# Integrated_LED.net
KiCad netlist of a schematic drawn in Altium Designer
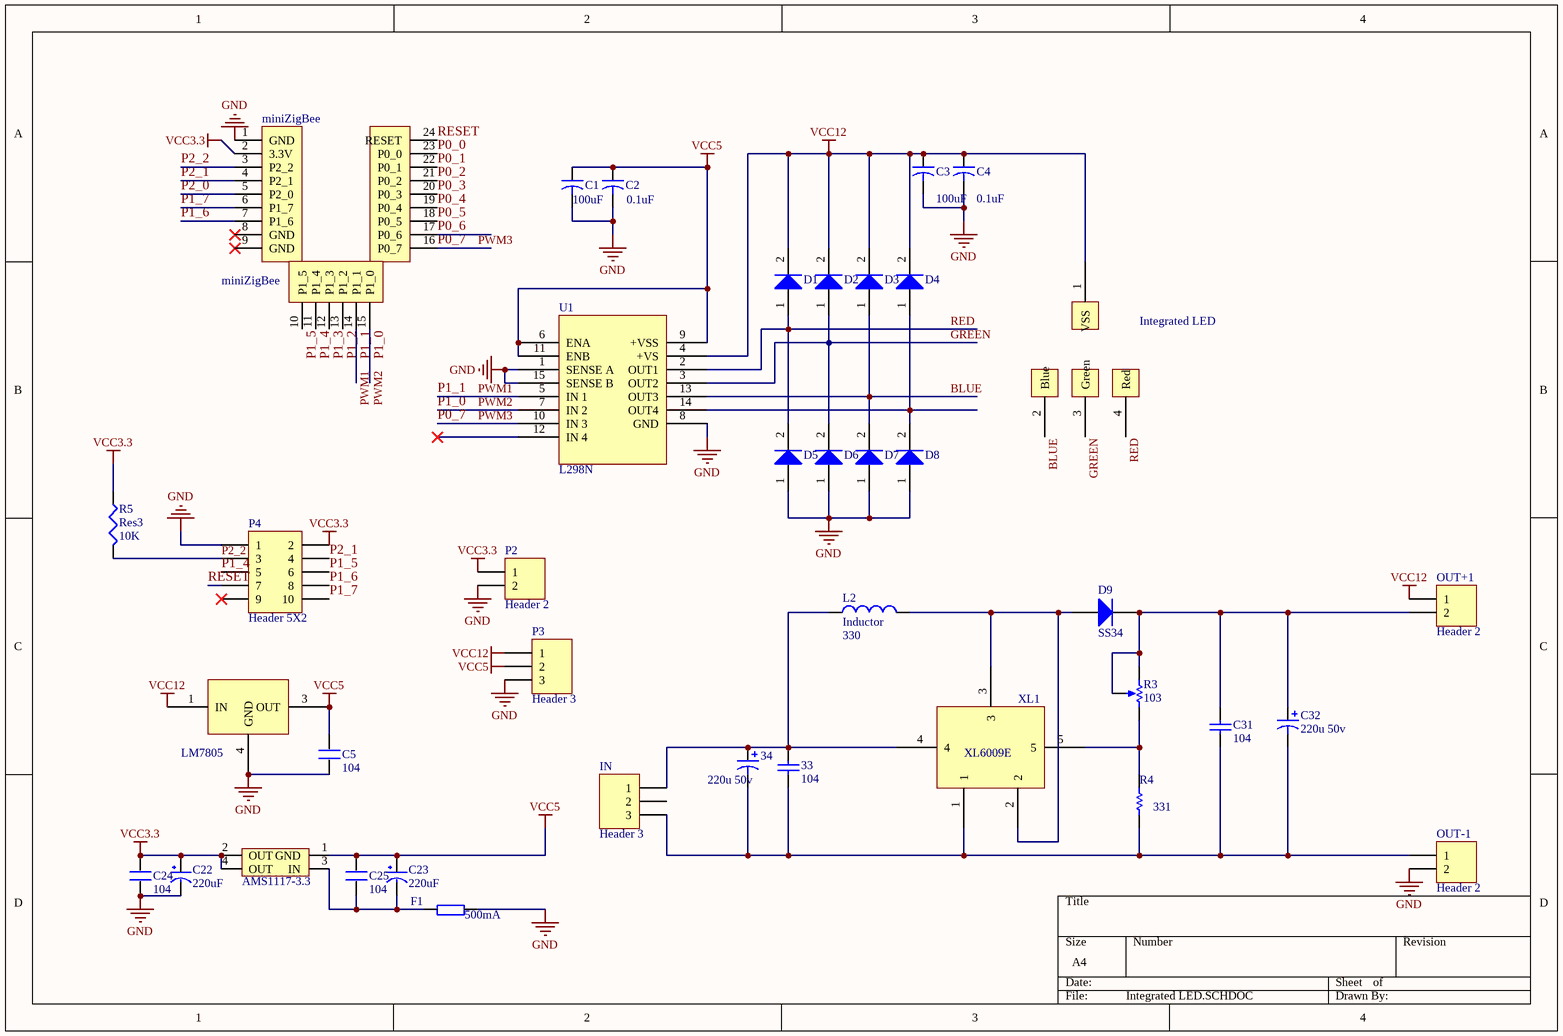
[diagram p0: Integrated LED.SCHDOC]

(export (version "E")
  (design (tool "Eeschema 10.0.6"))
  (components
    (comp (ref "33")
      (value "104")
      (footprint "0805")
      (description "Capacitor")
      (fields (field (name "PUBLISHER") "Altium Limited"))
      (libsource (lib "Miscellaneous Devices") (part "Cap"))
    )
    (comp (ref "34")
      (value "220u 50v")
      (footprint "贴片电解电容")
      (description "Polarized Capacitor (Radial)")
      (fields (field (name "PUBLISHER") "Altium Limited"))
      (libsource (lib "Miscellaneous Devices") (part "Cap Pol1"))
    )
    (comp (ref "C1")
      (value "100uF")
      (footprint "PCBComponent_1")
      (description "Capacitor")
      (fields (field (name "PUBLISHER") "Altium Limited"))
      (libsource (lib "Miscellaneous Devices") (part "Cap2"))
    )
    (comp (ref "C2")
      (value "0.1uF")
      (footprint "PCBComponent_1")
      (description "Capacitor")
      (fields (field (name "PUBLISHER") "Altium Limited"))
      (libsource (lib "Miscellaneous Devices") (part "Cap2"))
    )
    (comp (ref "C3")
      (value "100uF")
      (footprint "PCBComponent_1")
      (description "Capacitor")
      (fields (field (name "PUBLISHER") "Altium Limited"))
      (libsource (lib "Miscellaneous Devices") (part "Cap2"))
    )
    (comp (ref "C4")
      (value "0.1uF")
      (footprint "PCBComponent_1")
      (description "Capacitor")
      (fields (field (name "PUBLISHER") "Altium Limited"))
      (libsource (lib "Miscellaneous Devices") (part "Cap2"))
    )
    (comp (ref "C5") (value "104") (footprint "0603P") (libsource (lib "my Integrated lib ") (part "C")))
    (comp (ref "C22")
      (value "220uF")
      (footprint "CC6.56.5")
      (libsource (lib "MiniSTM32 V2.0封装库") (part "CAP"))
    )
    (comp (ref "C23")
      (value "220uF")
      (footprint "CC6.56.5")
      (libsource (lib "MiniSTM32 V2.0封装库") (part "CAP"))
    )
    (comp (ref "C24") (value "104") (footprint "0603P") (libsource (lib "MiniSTM32 V2.0封装库") (part "C")))
    (comp (ref "C25") (value "104") (footprint "0603P") (libsource (lib "MiniSTM32 V2.0封装库") (part "C")))
    (comp (ref "C31")
      (value "104")
      (footprint "0805")
      (description "Capacitor")
      (fields (field (name "PUBLISHER") "Altium Limited"))
      (libsource (lib "Miscellaneous Devices") (part "Cap"))
    )
    (comp (ref "C32")
      (value "220u 50v")
      (footprint "贴片电解电容")
      (description "Polarized Capacitor (Radial)")
      (fields (field (name "PUBLISHER") "Altium Limited"))
      (libsource (lib "Miscellaneous Devices") (part "Cap Pol1"))
    )
    (comp (ref "D1")
      (value "IN4007")
      (footprint "IN4007")
      (libsource (lib "my Integrated lib ") (part "IN4007"))
    )
    (comp (ref "D2")
      (value "IN4007")
      (footprint "IN4007")
      (libsource (lib "my Integrated lib ") (part "IN4007"))
    )
    (comp (ref "D3")
      (value "IN4007")
      (footprint "IN4007")
      (libsource (lib "my Integrated lib ") (part "IN4007"))
    )
    (comp (ref "D4")
      (value "IN4007")
      (footprint "IN4007")
      (libsource (lib "my Integrated lib ") (part "IN4007"))
    )
    (comp (ref "D5")
      (value "IN4007")
      (footprint "IN4007")
      (libsource (lib "my Integrated lib ") (part "IN4007"))
    )
    (comp (ref "D6")
      (value "IN4007")
      (footprint "IN4007")
      (libsource (lib "my Integrated lib ") (part "IN4007"))
    )
    (comp (ref "D7")
      (value "IN4007")
      (footprint "IN4007")
      (libsource (lib "my Integrated lib ") (part "IN4007"))
    )
    (comp (ref "D8")
      (value "IN4007")
      (footprint "IN4007")
      (libsource (lib "my Integrated lib ") (part "IN4007"))
    )
    (comp (ref "D9")
      (value "SS34")
      (footprint "SMC")
      (description "Default Diode")
      (fields (field (name "PUBLISHER") "Altium Limited"))
      (libsource (lib "Miscellaneous Devices") (part "Diode"))
    )
    (comp (ref "F1") (value "500mA") (footprint "0603P") (libsource (lib "MiniSTM32 V2.0封装库") (part "R")))
    (comp (ref "IN")
      (value "Header 3")
      (footprint "HDR1X3")
      (description "Header, 3-Pin")
      (fields (field (name "PUBLISHER") "Altium Limited"))
      (libsource (lib "") (part "Header 3_1"))
    )
    (comp (ref "Integrated LED")
      (value "Integrated LED")
      (footprint "Integrated LED")
      (libsource (lib "my Integrated lib ") (part "Integrated LED"))
    )
    (comp (ref "L2")
      (value "Inductor")
      (footprint "l")
      (fields (field (name "ALTIUM_VALUE") "330") (field (name "PUBLISHER") "Altium Limited"))
      (libsource (lib "Miscellaneous Devices") (part "Inductor"))
    )
    (comp (ref "LM7805")
      (value "LM7805")
      (footprint "LM7805")
      (libsource (lib "my Integrated lib ") (part "LM7805"))
    )
    (comp (ref "miniZigBee")
      (value "miniZigBee")
      (footprint "miniZigBee")
      (libsource (lib "my Integrated lib ") (part "miniZigBee"))
    )
    (comp (ref "OUT+1")
      (value "Header 2")
      (footprint "HDR1X2")
      (description "Header, 2-Pin")
      (fields (field (name "PUBLISHER") "Altium Limited"))
      (libsource (lib "Miscellaneous Connectors") (part "Header 2"))
    )
    (comp (ref "OUT-1")
      (value "Header 2")
      (footprint "HDR1X2")
      (description "Header, 2-Pin")
      (fields (field (name "PUBLISHER") "Altium Limited"))
      (libsource (lib "Miscellaneous Connectors") (part "Header 2"))
    )
    (comp (ref "P2")
      (value "Header 2")
      (footprint "HDR1X2")
      (description "Header, 2-Pin")
      (fields (field (name "PUBLISHER") "Altium Limited"))
      (libsource (lib "Miscellaneous Connectors") (part "Header 2"))
    )
    (comp (ref "P3")
      (value "Header 3")
      (footprint "HDR1X3")
      (description "Header, 3-Pin")
      (fields (field (name "PUBLISHER") "Altium Limited"))
      (libsource (lib "Miscellaneous Connectors") (part "Header 3"))
    )
    (comp (ref "P4")
      (value "Header 5X2")
      (footprint "HDR2X5")
      (description "Header, 5-Pin, Dual row")
      (fields (field (name "PUBLISHER") "Altium Limited"))
      (libsource (lib "Miscellaneous Connectors") (part "Header 5X2"))
    )
    (comp (ref "R3")
      (value "103")
      (footprint "VR4")
      (description "Potentiometer")
      (fields (field (name "PUBLISHER") "Altium Limited"))
      (libsource (lib "Miscellaneous Devices") (part "RPot"))
    )
    (comp (ref "R4")
      (value "331")
      (footprint "0805")
      (description "Resistor")
      (fields (field (name "PUBLISHER") "Altium Limited"))
      (libsource (lib "Miscellaneous Devices") (part "Res1"))
    )
    (comp (ref "R5")
      (value "Res3")
      (footprint "J1-0603")
      (description "Resistor")
      (fields (field (name "ALTIUM_VALUE") "10K") (field (name "PUBLISHER") "Altium Limited"))
      (libsource (lib "Miscellaneous Devices") (part "Res3"))
    )
    (comp (ref "U1") (value "L298N") (footprint "L298N - duplicate") (libsource (lib "KU1") (part "L298N")))
    (comp (ref "U6")
      (value "AMS1117-3.3")
      (footprint "AMS1117")
      (libsource (lib "my Integrated lib ") (part "AMS1117"))
    )
    (comp (ref "XL1") (value "XL6009e") (footprint "XL6003") (libsource (lib "*") (part "XL6009e")))
  )
  (nets
    (net (code "1") (name "/BLUE") (class "Default")
      (node (ref "D3") (pin "1") (pinfunction "A_1") (pintype "passive"))
      (node (ref "D7") (pin "2") (pinfunction "K_2") (pintype "passive"))
      (node (ref "Integrated LED") (pin "2") (pinfunction "Blue_2") (pintype "passive"))
      (node (ref "U1") (pin "13") (pinfunction "OUT3_13") (pintype "passive"))
    )
    (net (code "2") (name "/GREEN") (class "Default")
      (node (ref "D2") (pin "1") (pinfunction "A_1") (pintype "passive"))
      (node (ref "D6") (pin "2") (pinfunction "K_2") (pintype "passive"))
      (node (ref "Integrated LED") (pin "3") (pinfunction "Green_3") (pintype "passive"))
      (node (ref "U1") (pin "3") (pinfunction "OUT2_3") (pintype "passive"))
    )
    (net (code "3") (name "/P0_0") (class "Default")
      (node (ref "miniZigBee") (pin "23") (pinfunction "P0_0_23") (pintype "passive"))
    )
    (net (code "4") (name "/P0_1") (class "Default")
      (node (ref "miniZigBee") (pin "22") (pinfunction "P0_1_22") (pintype "passive"))
    )
    (net (code "5") (name "/P0_2") (class "Default")
      (node (ref "miniZigBee") (pin "21") (pinfunction "P0_2_21") (pintype "passive"))
    )
    (net (code "6") (name "/P0_3") (class "Default")
      (node (ref "miniZigBee") (pin "20") (pinfunction "P0_3_20") (pintype "passive"))
    )
    (net (code "7") (name "/P0_4") (class "Default")
      (node (ref "miniZigBee") (pin "19") (pinfunction "P0_4_19") (pintype "passive"))
    )
    (net (code "8") (name "/P0_5") (class "Default")
      (node (ref "miniZigBee") (pin "18") (pinfunction "P0_5_18") (pintype "passive"))
    )
    (net (code "9") (name "/P0_6") (class "Default")
      (node (ref "miniZigBee") (pin "17") (pinfunction "P0_6_17") (pintype "passive"))
    )
    (net (code "10") (name "/P0_7") (class "Default")
      (node (ref "U1") (pin "10") (pinfunction "IN_3_10") (pintype "passive"))
      (node (ref "miniZigBee") (pin "16") (pinfunction "P0_7_16") (pintype "passive"))
    )
    (net (code "11") (name "/P1_0") (class "Default")
      (node (ref "U1") (pin "7") (pinfunction "IN_2_7") (pintype "passive"))
      (node (ref "miniZigBee") (pin "15") (pinfunction "P1_0_15") (pintype "passive"))
    )
    (net (code "12") (name "/P1_1") (class "Default")
      (node (ref "U1") (pin "5") (pinfunction "IN_1_5") (pintype "passive"))
      (node (ref "miniZigBee") (pin "14") (pinfunction "P1_1_14") (pintype "passive"))
    )
    (net (code "13") (name "/P1_2") (class "Default")
      (node (ref "miniZigBee") (pin "13") (pinfunction "P1_2_13") (pintype "passive"))
    )
    (net (code "14") (name "/P1_3") (class "Default")
      (node (ref "miniZigBee") (pin "12") (pinfunction "P1_3_12") (pintype "passive"))
    )
    (net (code "15") (name "/P1_4") (class "Default")
      (node (ref "P4") (pin "5") (pinfunction "5_5") (pintype "passive"))
      (node (ref "miniZigBee") (pin "11") (pinfunction "P1_4_11") (pintype "passive"))
    )
    (net (code "16") (name "/P1_5") (class "Default")
      (node (ref "P4") (pin "6") (pinfunction "6_6") (pintype "passive"))
      (node (ref "miniZigBee") (pin "10") (pinfunction "P1_5_10") (pintype "passive"))
    )
    (net (code "17") (name "/P1_6") (class "Default")
      (node (ref "P4") (pin "8") (pinfunction "8_8") (pintype "passive"))
      (node (ref "miniZigBee") (pin "7") (pinfunction "P1_6_7") (pintype "passive"))
    )
    (net (code "18") (name "/P1_7") (class "Default")
      (node (ref "P4") (pin "10") (pinfunction "10_10") (pintype "passive"))
      (node (ref "miniZigBee") (pin "6") (pinfunction "P1_7_6") (pintype "passive"))
    )
    (net (code "19") (name "/P2_0") (class "Default")
      (node (ref "miniZigBee") (pin "5") (pinfunction "P2_0_5") (pintype "passive"))
    )
    (net (code "20") (name "/P2_1") (class "Default")
      (node (ref "P4") (pin "4") (pinfunction "4_4") (pintype "passive"))
      (node (ref "miniZigBee") (pin "4") (pinfunction "P2_1_4") (pintype "passive"))
    )
    (net (code "21") (name "/P2_2") (class "Default")
      (node (ref "P4") (pin "3") (pinfunction "3_3") (pintype "passive"))
      (node (ref "R5") (pin "2") (pinfunction "2_2") (pintype "passive"))
      (node (ref "miniZigBee") (pin "3") (pinfunction "P2_2_3") (pintype "passive"))
    )
    (net (code "22") (name "/RED") (class "Default")
      (node (ref "D1") (pin "1") (pinfunction "A_1") (pintype "passive"))
      (node (ref "D5") (pin "2") (pinfunction "K_2") (pintype "passive"))
      (node (ref "Integrated LED") (pin "4") (pinfunction "Red_4") (pintype "passive"))
      (node (ref "U1") (pin "2") (pinfunction "OUT1_2") (pintype "passive"))
    )
    (net (code "23") (name "/RESET") (class "Default")
      (node (ref "P4") (pin "7") (pinfunction "7_7") (pintype "passive"))
      (node (ref "miniZigBee") (pin "24") (pinfunction "RESET_24") (pintype "passive"))
    )
    (net (code "24") (name "GND") (class "Default")
      (node (ref "C1") (pin "2") (pinfunction "2_2") (pintype "passive"))
      (node (ref "C2") (pin "2") (pinfunction "2_2") (pintype "passive"))
      (node (ref "C22") (pin "2") (pinfunction "GND_2") (pintype "passive"))
      (node (ref "C24") (pin "1") (pintype "passive"))
      (node (ref "C3") (pin "2") (pinfunction "2_2") (pintype "passive"))
      (node (ref "C4") (pin "2") (pinfunction "2_2") (pintype "passive"))
      (node (ref "C5") (pin "1") (pintype "passive"))
      (node (ref "D5") (pin "1") (pinfunction "A_1") (pintype "passive"))
      (node (ref "D6") (pin "1") (pinfunction "A_1") (pintype "passive"))
      (node (ref "D7") (pin "1") (pinfunction "A_1") (pintype "passive"))
      (node (ref "D8") (pin "1") (pinfunction "A_1") (pintype "passive"))
      (node (ref "F1") (pin "2") (pintype "passive"))
      (node (ref "LM7805") (pin "4") (pinfunction "GND_4") (pintype "passive"))
      (node (ref "OUT-1") (pin "2") (pinfunction "2_2") (pintype "passive"))
      (node (ref "P2") (pin "2") (pinfunction "2_2") (pintype "passive"))
      (node (ref "P3") (pin "3") (pinfunction "3_3") (pintype "passive"))
      (node (ref "P4") (pin "1") (pinfunction "1_1") (pintype "passive"))
      (node (ref "U1") (pin "1") (pinfunction "SENSE_A_1") (pintype "passive"))
      (node (ref "U1") (pin "15") (pinfunction "SENSE_B_15") (pintype "passive"))
      (node (ref "U1") (pin "8") (pinfunction "GND_8") (pintype "passive"))
      (node (ref "miniZigBee") (pin "1") (pinfunction "GND_1") (pintype "passive"))
    )
    (net (code "25") (name "Net-(33-Pad1)") (class "Default")
      (node (ref "33") (pin "1") (pinfunction "1_1") (pintype "passive"))
      (node (ref "34") (pin "2") (pinfunction "2_2") (pintype "passive"))
      (node (ref "C31") (pin "1") (pinfunction "1_1") (pintype "passive"))
      (node (ref "C32") (pin "2") (pinfunction "2_2") (pintype "passive"))
      (node (ref "IN") (pin "3") (pinfunction "3_3") (pintype "passive"))
      (node (ref "OUT-1") (pin "1") (pinfunction "1_1") (pintype "passive"))
      (node (ref "R4") (pin "1") (pinfunction "1_1") (pintype "passive"))
      (node (ref "XL1") (pin "1") (pinfunction "1_1") (pintype "passive"))
    )
    (net (code "26") (name "Net-(33-Pad2)") (class "Default")
      (node (ref "33") (pin "2") (pinfunction "2_2") (pintype "passive"))
      (node (ref "34") (pin "1") (pinfunction "1_1") (pintype "passive"))
      (node (ref "IN") (pin "1") (pinfunction "1_1") (pintype "passive"))
      (node (ref "L2") (pin "1") (pinfunction "1_1") (pintype "passive"))
      (node (ref "XL1") (pin "4") (pinfunction "4_4") (pintype "passive"))
    )
    (net (code "27") (name "Net-(C23-GND)") (class "Default")
      (node (ref "C23") (pin "2") (pinfunction "GND_2") (pintype "passive"))
      (node (ref "C25") (pin "1") (pintype "passive"))
      (node (ref "F1") (pin "1") (pintype "passive"))
      (node (ref "U6") (pin "3") (pinfunction "IN_3") (pintype "passive"))
    )
    (net (code "28") (name "Net-(D4-A)") (class "Default")
      (node (ref "D4") (pin "1") (pinfunction "A_1") (pintype "passive"))
      (node (ref "D8") (pin "2") (pinfunction "K_2") (pintype "passive"))
      (node (ref "U1") (pin "14") (pinfunction "OUT4_14") (pintype "passive"))
    )
    (net (code "29") (name "Net-(D9-A)") (class "Default")
      (node (ref "D9") (pin "1") (pinfunction "A_1") (pintype "passive"))
      (node (ref "L2") (pin "0") (pinfunction "0_0") (pintype "passive"))
      (node (ref "XL1") (pin "2") (pinfunction "2_2") (pintype "passive"))
      (node (ref "XL1") (pin "3") (pinfunction "3_3") (pintype "passive"))
    )
    (net (code "30") (name "Net-(D9-K)") (class "Default")
      (node (ref "C31") (pin "2") (pinfunction "2_2") (pintype "passive"))
      (node (ref "C32") (pin "1") (pinfunction "1_1") (pintype "passive"))
      (node (ref "D9") (pin "2") (pinfunction "K_2") (pintype "passive"))
      (node (ref "OUT+1") (pin "2") (pinfunction "2_2") (pintype "passive"))
      (node (ref "R3") (pin "2") (pinfunction "TAP_2") (pintype "passive"))
      (node (ref "R3") (pin "3") (pinfunction "TOP_3") (pintype "passive"))
    )
    (net (code "31") (name "Net-(R3-BOT)") (class "Default")
      (node (ref "R3") (pin "1") (pinfunction "BOT_1") (pintype "passive"))
      (node (ref "R4") (pin "2") (pinfunction "2_2") (pintype "passive"))
      (node (ref "XL1") (pin "5") (pinfunction "5_5") (pintype "passive"))
    )
    (net (code "32") (name "VCC3.3") (class "Default")
      (node (ref "C22") (pin "1") (pinfunction "VCC_1") (pintype "passive"))
      (node (ref "C24") (pin "2") (pintype "passive"))
      (node (ref "P2") (pin "1") (pinfunction "1_1") (pintype "passive"))
      (node (ref "P4") (pin "2") (pinfunction "2_2") (pintype "passive"))
      (node (ref "R5") (pin "1") (pinfunction "1_1") (pintype "passive"))
      (node (ref "U6") (pin "2") (pinfunction "OUT_2") (pintype "passive"))
      (node (ref "U6") (pin "4") (pinfunction "OUT_4") (pintype "passive"))
      (node (ref "miniZigBee") (pin "2") (pinfunction "3.3V_2") (pintype "passive"))
    )
    (net (code "33") (name "VCC5") (class "Default")
      (node (ref "C1") (pin "1") (pinfunction "1_1") (pintype "passive"))
      (node (ref "C2") (pin "1") (pinfunction "1_1") (pintype "passive"))
      (node (ref "C23") (pin "1") (pinfunction "VCC_1") (pintype "passive"))
      (node (ref "C25") (pin "2") (pintype "passive"))
      (node (ref "C5") (pin "2") (pintype "passive"))
      (node (ref "LM7805") (pin "3") (pinfunction "OUT_3") (pintype "passive"))
      (node (ref "P3") (pin "2") (pinfunction "2_2") (pintype "passive"))
      (node (ref "U1") (pin "11") (pinfunction "ENB_11") (pintype "passive"))
      (node (ref "U1") (pin "6") (pinfunction "ENA_6") (pintype "passive"))
      (node (ref "U1") (pin "9") (pinfunction "+VSS_9") (pintype "passive"))
      (node (ref "U6") (pin "1") (pinfunction "GND_1") (pintype "passive"))
    )
    (net (code "34") (name "VCC12") (class "Default")
      (node (ref "C3") (pin "1") (pinfunction "1_1") (pintype "passive"))
      (node (ref "C4") (pin "1") (pinfunction "1_1") (pintype "passive"))
      (node (ref "D1") (pin "2") (pinfunction "K_2") (pintype "passive"))
      (node (ref "D2") (pin "2") (pinfunction "K_2") (pintype "passive"))
      (node (ref "D3") (pin "2") (pinfunction "K_2") (pintype "passive"))
      (node (ref "D4") (pin "2") (pinfunction "K_2") (pintype "passive"))
      (node (ref "Integrated LED") (pin "1") (pinfunction "VSS_1") (pintype "passive"))
      (node (ref "LM7805") (pin "1") (pinfunction "IN_1") (pintype "passive"))
      (node (ref "OUT+1") (pin "1") (pinfunction "1_1") (pintype "passive"))
      (node (ref "P3") (pin "1") (pinfunction "1_1") (pintype "passive"))
      (node (ref "U1") (pin "4") (pinfunction "+VS_4") (pintype "passive"))
    )
    (net (code "35") (name "unconnected-(IN-Pad2)") (class "Default")
      (node (ref "IN") (pin "2") (pinfunction "2_2") (pintype "passive"))
    )
    (net (code "36") (name "unconnected-(P4-Pad9)") (class "Default")
      (node (ref "P4") (pin "9") (pinfunction "9_9") (pintype "passive+no_connect"))
    )
    (net (code "37") (name "unconnected-(U1-IN_4-Pad12)") (class "Default")
      (node (ref "U1") (pin "12") (pinfunction "IN_4_12") (pintype "passive+no_connect"))
    )
    (net (code "38") (name "unconnected-(miniZigBee-GND-Pad8)") (class "Default")
      (node (ref "miniZigBee") (pin "8") (pinfunction "GND_8") (pintype "passive+no_connect"))
    )
    (net (code "39") (name "unconnected-(miniZigBee-GND-Pad9)") (class "Default")
      (node (ref "miniZigBee") (pin "9") (pinfunction "GND_9") (pintype "passive+no_connect"))
    )
  )
)
